# top.net
KiCad netlist of a schematic drawn in Altium Designer
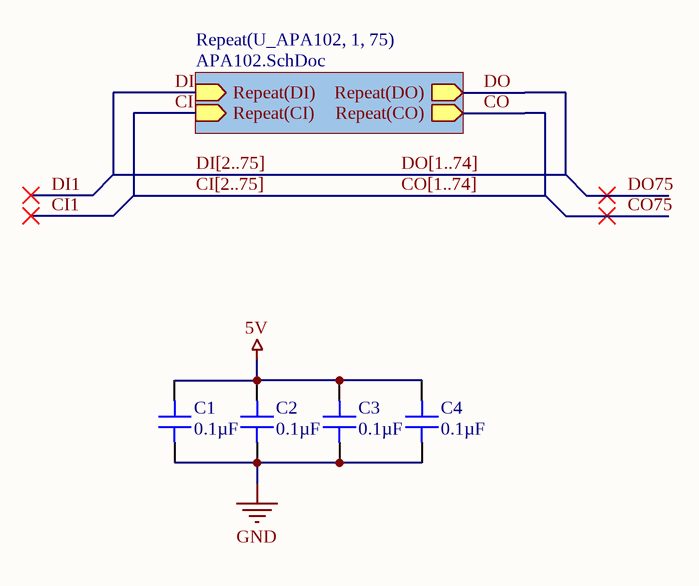
[diagram p0: top.SchDoc]

(export (version "E")
  (design (tool "Eeschema 10.0.6"))
  (components
    (comp (ref "C1")
      (value "0.1µF")
      (footprint "CAP 0402_1005")
      (description "CAP CER 0.1UF 16V Y5V 0402")
      (fields
        (field (name "PART NUMBER") "VJ0402V104ZXJCW1BC")
        (field (name "MANUFACTURER") "Vishay Vitramon")
      )
      (libsource (lib "Celestial Altium Library - altium_library") (part "Capacitor"))
    )
    (comp (ref "C2")
      (value "0.1µF")
      (footprint "CAP 0402_1005")
      (description "CAP CER 0.1UF 16V Y5V 0402")
      (fields
        (field (name "PART NUMBER") "VJ0402V104ZXJCW1BC")
        (field (name "MANUFACTURER") "Vishay Vitramon")
      )
      (libsource (lib "Celestial Altium Library - altium_library") (part "Capacitor"))
    )
    (comp (ref "C3")
      (value "0.1µF")
      (footprint "CAP 0402_1005")
      (description "CAP CER 0.1UF 16V Y5V 0402")
      (fields
        (field (name "PART NUMBER") "VJ0402V104ZXJCW1BC")
        (field (name "MANUFACTURER") "Vishay Vitramon")
      )
      (libsource (lib "Celestial Altium Library - altium_library") (part "Capacitor"))
    )
    (comp (ref "C4")
      (value "0.1µF")
      (footprint "CAP 0402_1005")
      (description "CAP CER 0.1UF 16V Y5V 0402")
      (fields
        (field (name "PART NUMBER") "VJ0402V104ZXJCW1BC")
        (field (name "MANUFACTURER") "Vishay Vitramon")
      )
      (libsource (lib "Celestial Altium Library - altium_library") (part "Capacitor"))
    )
  )
  (nets
    (net (code "159") (name "5V") (class "Default")
      (node (ref "C1") (pin "2") (pinfunction "2_2") (pintype "passive"))
      (node (ref "C2") (pin "2") (pinfunction "2_2") (pintype "passive"))
      (node (ref "C3") (pin "2") (pinfunction "2_2") (pintype "passive"))
      (node (ref "C4") (pin "2") (pinfunction "2_2") (pintype "passive"))
    )
    (net (code "160") (name "GND") (class "Default")
      (node (ref "C1") (pin "1") (pinfunction "1_1") (pintype "passive"))
      (node (ref "C2") (pin "1") (pinfunction "1_1") (pintype "passive"))
      (node (ref "C3") (pin "1") (pinfunction "1_1") (pintype "passive"))
      (node (ref "C4") (pin "1") (pinfunction "1_1") (pintype "passive"))
    )
  )
)
